# lh.net
KiCad netlist of a schematic drawn in EAGLE
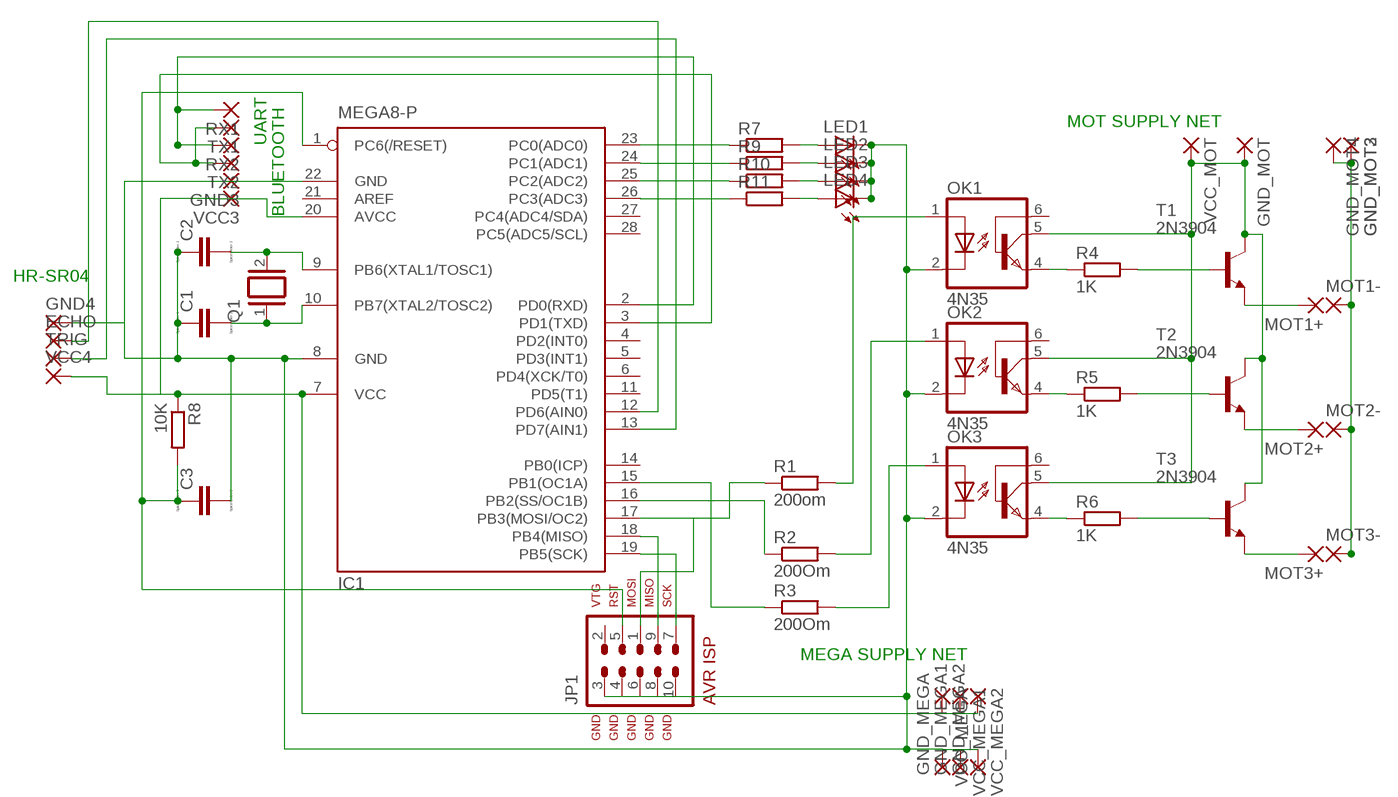
[diagram p0: schematic, sheet 1]

(export (version "E")
  (design (tool "Eeschema 10.0.6"))
  (components
    (comp (ref "C1")
      (value "CC1206")
      (footprint "eagle-import:C1206")
      (libsource (lib "eagle-import") (part "CC1206"))
    )
    (comp (ref "C2")
      (value "CC1206")
      (footprint "eagle-import:C1206")
      (libsource (lib "eagle-import") (part "CC1206"))
    )
    (comp (ref "C3")
      (value "CC1206")
      (footprint "eagle-import:C1206")
      (libsource (lib "eagle-import") (part "CC1206"))
    )
    (comp (ref "ECHO")
      (value "1,6/0,8")
      (footprint "eagle-import:1,6_0,8")
      (libsource (lib "eagle-import") (part "1,6/0,8"))
    )
    (comp (ref "GND3")
      (value "1,6/0,8")
      (footprint "eagle-import:1,6_0,8")
      (libsource (lib "eagle-import") (part "1,6/0,8"))
    )
    (comp (ref "GND4")
      (value "1,6/0,8")
      (footprint "eagle-import:1,6_0,8")
      (libsource (lib "eagle-import") (part "1,6/0,8"))
    )
    (comp (ref "GND_MEGA")
      (value "1,6/0,8")
      (footprint "eagle-import:1,6_0,8")
      (libsource (lib "eagle-import") (part "1,6/0,8"))
    )
    (comp (ref "GND_MEGA1")
      (value "1,6/0,8")
      (footprint "eagle-import:1,6_0,8")
      (libsource (lib "eagle-import") (part "1,6/0,8"))
    )
    (comp (ref "GND_MEGA2")
      (value "1,6/0,8")
      (footprint "eagle-import:1,6_0,8")
      (libsource (lib "eagle-import") (part "1,6/0,8"))
    )
    (comp (ref "GND_MOT")
      (value "1,6/0,8")
      (footprint "eagle-import:1,6_0,8")
      (libsource (lib "eagle-import") (part "1,6/0,8"))
    )
    (comp (ref "GND_MOT2")
      (value "1,6/0,8")
      (footprint "eagle-import:1,6_0,8")
      (libsource (lib "eagle-import") (part "1,6/0,8"))
    )
    (comp (ref "GND_MOT3")
      (value "1,6/0,8")
      (footprint "eagle-import:1,6_0,8")
      (libsource (lib "eagle-import") (part "1,6/0,8"))
    )
    (comp (ref "GND_MOT4")
      (value "1,6/0,8")
      (footprint "eagle-import:1,6_0,8")
      (libsource (lib "eagle-import") (part "1,6/0,8"))
    )
    (comp (ref "IC1")
      (value "MEGA8-P")
      (footprint "eagle-import:DIL28-3")
      (libsource (lib "eagle-import") (part "MEGA8-P"))
    )
    (comp (ref "JP1")
      (value "AVR-ISP-10")
      (footprint "eagle-import:AVR-ISP-10")
      (libsource (lib "eagle-import") (part "AVR-ISP-10"))
    )
    (comp (ref "LED1")
      (value "LEDSML0603")
      (footprint "eagle-import:SML0603")
      (libsource (lib "eagle-import") (part "LEDSML0603"))
    )
    (comp (ref "LED2")
      (value "LEDSML0603")
      (footprint "eagle-import:SML0603")
      (libsource (lib "eagle-import") (part "LEDSML0603"))
    )
    (comp (ref "LED3")
      (value "LEDSML0603")
      (footprint "eagle-import:SML0603")
      (libsource (lib "eagle-import") (part "LEDSML0603"))
    )
    (comp (ref "LED4")
      (value "LEDSML0603")
      (footprint "eagle-import:SML0603")
      (libsource (lib "eagle-import") (part "LEDSML0603"))
    )
    (comp (ref "MOT1+")
      (value "1,6/0,8")
      (footprint "eagle-import:1,6_0,8")
      (libsource (lib "eagle-import") (part "1,6/0,8"))
    )
    (comp (ref "MOT1-")
      (value "1,6/0,8")
      (footprint "eagle-import:1,6_0,8")
      (libsource (lib "eagle-import") (part "1,6/0,8"))
    )
    (comp (ref "MOT2+")
      (value "1,6/0,8")
      (footprint "eagle-import:1,6_0,8")
      (libsource (lib "eagle-import") (part "1,6/0,8"))
    )
    (comp (ref "MOT2-")
      (value "1,6/0,8")
      (footprint "eagle-import:1,6_0,8")
      (libsource (lib "eagle-import") (part "1,6/0,8"))
    )
    (comp (ref "MOT3+")
      (value "1,6/0,8")
      (footprint "eagle-import:1,6_0,8")
      (libsource (lib "eagle-import") (part "1,6/0,8"))
    )
    (comp (ref "MOT3-")
      (value "1,6/0,8")
      (footprint "eagle-import:1,6_0,8")
      (libsource (lib "eagle-import") (part "1,6/0,8"))
    )
    (comp (ref "OK1")
      (value "4N35")
      (footprint "eagle-import:DIL06")
      (fields (field (name "MF") "FAIRCHILD SEMICONDUCTOR"))
      (libsource (lib "eagle-import") (part "4N35"))
    )
    (comp (ref "OK2")
      (value "4N35")
      (footprint "eagle-import:DIL06")
      (fields (field (name "MF") "FAIRCHILD SEMICONDUCTOR"))
      (libsource (lib "eagle-import") (part "4N35"))
    )
    (comp (ref "OK3")
      (value "4N35")
      (footprint "eagle-import:DIL06")
      (fields (field (name "MF") "FAIRCHILD SEMICONDUCTOR"))
      (libsource (lib "eagle-import") (part "4N35"))
    )
    (comp (ref "Q1")
      (value "XTAL/S")
      (footprint "eagle-import:QS")
      (libsource (lib "eagle-import") (part "XTAL/S"))
    )
    (comp (ref "R1")
      (value "200om")
      (footprint "eagle-import:R0603")
      (libsource (lib "eagle-import") (part "R-EU_R0603"))
    )
    (comp (ref "R2")
      (value "200Om")
      (footprint "eagle-import:R0603")
      (libsource (lib "eagle-import") (part "R-EU_R0603"))
    )
    (comp (ref "R3")
      (value "200Om")
      (footprint "eagle-import:R0603")
      (libsource (lib "eagle-import") (part "R-EU_R0603"))
    )
    (comp (ref "R4")
      (value "1K")
      (footprint "eagle-import:R0603")
      (libsource (lib "eagle-import") (part "R-EU_R0603"))
    )
    (comp (ref "R5")
      (value "1K")
      (footprint "eagle-import:R0603")
      (libsource (lib "eagle-import") (part "R-EU_R0603"))
    )
    (comp (ref "R6")
      (value "1K")
      (footprint "eagle-import:R0603")
      (libsource (lib "eagle-import") (part "R-EU_R0603"))
    )
    (comp (ref "R7")
      (value "R-EU_R0603")
      (footprint "eagle-import:R0603")
      (libsource (lib "eagle-import") (part "R-EU_R0603"))
    )
    (comp (ref "R8")
      (value "10K")
      (footprint "eagle-import:R0603")
      (libsource (lib "eagle-import") (part "R-EU_R0603"))
    )
    (comp (ref "R9")
      (value "R-EU_R0603")
      (footprint "eagle-import:R0603")
      (libsource (lib "eagle-import") (part "R-EU_R0603"))
    )
    (comp (ref "R10")
      (value "R-EU_R0603")
      (footprint "eagle-import:R0603")
      (libsource (lib "eagle-import") (part "R-EU_R0603"))
    )
    (comp (ref "R11")
      (value "R-EU_R0603")
      (footprint "eagle-import:R0603")
      (libsource (lib "eagle-import") (part "R-EU_R0603"))
    )
    (comp (ref "RX1")
      (value "1,6/0,8")
      (footprint "eagle-import:1,6_0,8")
      (libsource (lib "eagle-import") (part "1,6/0,8"))
    )
    (comp (ref "RX2")
      (value "1,6/0,8")
      (footprint "eagle-import:1,6_0,8")
      (libsource (lib "eagle-import") (part "1,6/0,8"))
    )
    (comp (ref "T1")
      (value "2N3904")
      (footprint "eagle-import:TO92")
      (libsource (lib "eagle-import") (part "2N3904"))
    )
    (comp (ref "T2")
      (value "2N3904")
      (footprint "eagle-import:TO92")
      (libsource (lib "eagle-import") (part "2N3904"))
    )
    (comp (ref "T3")
      (value "2N3904")
      (footprint "eagle-import:TO92")
      (libsource (lib "eagle-import") (part "2N3904"))
    )
    (comp (ref "TRIG")
      (value "1,6/0,8")
      (footprint "eagle-import:1,6_0,8")
      (libsource (lib "eagle-import") (part "1,6/0,8"))
    )
    (comp (ref "TX1")
      (value "1,6/0,8")
      (footprint "eagle-import:1,6_0,8")
      (libsource (lib "eagle-import") (part "1,6/0,8"))
    )
    (comp (ref "TX2")
      (value "1,6/0,8")
      (footprint "eagle-import:1,6_0,8")
      (libsource (lib "eagle-import") (part "1,6/0,8"))
    )
    (comp (ref "VCC3")
      (value "1,6/0,8")
      (footprint "eagle-import:1,6_0,8")
      (libsource (lib "eagle-import") (part "1,6/0,8"))
    )
    (comp (ref "VCC4")
      (value "1,6/0,8")
      (footprint "eagle-import:1,6_0,8")
      (libsource (lib "eagle-import") (part "1,6/0,8"))
    )
    (comp (ref "VCC_MEGA")
      (value "1,6/0,8")
      (footprint "eagle-import:1,6_0,8")
      (libsource (lib "eagle-import") (part "1,6/0,8"))
    )
    (comp (ref "VCC_MEGA1")
      (value "1,6/0,8")
      (footprint "eagle-import:1,6_0,8")
      (libsource (lib "eagle-import") (part "1,6/0,8"))
    )
    (comp (ref "VCC_MEGA2")
      (value "1,6/0,8")
      (footprint "eagle-import:1,6_0,8")
      (libsource (lib "eagle-import") (part "1,6/0,8"))
    )
    (comp (ref "VCC_MOT")
      (value "1,6/0,8")
      (footprint "eagle-import:1,6_0,8")
      (libsource (lib "eagle-import") (part "1,6/0,8"))
    )
  )
  (nets
    (net (code "1") (name "Net-(ECHO-P)") (class "Default")
      (node (ref "ECHO") (pin "1") (pinfunction "P_1") (pintype "passive"))
      (node (ref "IC1") (pin "12") (pinfunction "PD6(AIN0)_12") (pintype "bidirectional"))
    )
    (net (code "2") (name "Net-(GND3-P)") (class "Default")
      (node (ref "C1") (pin "1") (pinfunction "1_1") (pintype "passive"))
      (node (ref "C2") (pin "1") (pinfunction "1_1") (pintype "passive"))
      (node (ref "C3") (pin "2") (pinfunction "2_2") (pintype "passive"))
      (node (ref "GND3") (pin "1") (pinfunction "P_1") (pintype "passive"))
      (node (ref "GND4") (pin "1") (pinfunction "P_1") (pintype "passive"))
      (node (ref "GND_MEGA") (pin "1") (pinfunction "P_1") (pintype "passive"))
      (node (ref "GND_MEGA1") (pin "1") (pinfunction "P_1") (pintype "passive"))
      (node (ref "GND_MEGA2") (pin "1") (pinfunction "P_1") (pintype "passive"))
      (node (ref "IC1") (pin "22") (pinfunction "GND_22") (pintype "power_in"))
      (node (ref "IC1") (pin "8") (pinfunction "GND_8") (pintype "power_in"))
      (node (ref "JP1") (pin "10") (pinfunction "10_10") (pintype "passive"))
      (node (ref "JP1") (pin "3") (pinfunction "3_3") (pintype "passive"))
      (node (ref "JP1") (pin "4") (pinfunction "4_4") (pintype "passive"))
      (node (ref "JP1") (pin "6") (pinfunction "6_6") (pintype "passive"))
      (node (ref "JP1") (pin "8") (pinfunction "8_8") (pintype "passive"))
      (node (ref "LED1") (pin "C") (pinfunction "C_C") (pintype "passive"))
      (node (ref "LED2") (pin "C") (pinfunction "C_C") (pintype "passive"))
      (node (ref "LED3") (pin "C") (pinfunction "C_C") (pintype "passive"))
      (node (ref "LED4") (pin "C") (pinfunction "C_C") (pintype "passive"))
      (node (ref "OK1") (pin "2") (pinfunction "C_2") (pintype "passive"))
      (node (ref "OK2") (pin "2") (pinfunction "C_2") (pintype "passive"))
      (node (ref "OK3") (pin "2") (pinfunction "C_2") (pintype "passive"))
    )
    (net (code "3") (name "Net-(GND_MOT-P)") (class "Default")
      (node (ref "GND_MOT") (pin "1") (pinfunction "P_1") (pintype "passive"))
      (node (ref "OK1") (pin "5") (pinfunction "COL_5") (pintype "passive"))
      (node (ref "OK2") (pin "5") (pinfunction "COL_5") (pintype "passive"))
      (node (ref "OK3") (pin "5") (pinfunction "COL_5") (pintype "passive"))
      (node (ref "T1") (pin "1") (pinfunction "C_1") (pintype "passive"))
      (node (ref "T2") (pin "1") (pinfunction "C_1") (pintype "passive"))
      (node (ref "T3") (pin "1") (pinfunction "C_1") (pintype "passive"))
      (node (ref "VCC_MOT") (pin "1") (pinfunction "P_1") (pintype "passive"))
    )
    (net (code "4") (name "Net-(GND_MOT2-P)") (class "Default")
      (node (ref "GND_MOT2") (pin "1") (pinfunction "P_1") (pintype "passive"))
      (node (ref "GND_MOT3") (pin "1") (pinfunction "P_1") (pintype "passive"))
      (node (ref "GND_MOT4") (pin "1") (pinfunction "P_1") (pintype "passive"))
      (node (ref "MOT1-") (pin "1") (pinfunction "P_1") (pintype "passive"))
      (node (ref "MOT2-") (pin "1") (pinfunction "P_1") (pintype "passive"))
      (node (ref "MOT3-") (pin "1") (pinfunction "P_1") (pintype "passive"))
    )
    (net (code "5") (name "Net-(IC1-AVCC)") (class "Default")
      (node (ref "IC1") (pin "20") (pinfunction "AVCC_20") (pintype "power_in"))
      (node (ref "IC1") (pin "7") (pinfunction "VCC_7") (pintype "power_in"))
      (node (ref "R8") (pin "1") (pinfunction "1_1") (pintype "passive"))
      (node (ref "VCC3") (pin "1") (pinfunction "P_1") (pintype "passive"))
      (node (ref "VCC4") (pin "1") (pinfunction "P_1") (pintype "passive"))
      (node (ref "VCC_MEGA") (pin "1") (pinfunction "P_1") (pintype "passive"))
      (node (ref "VCC_MEGA1") (pin "1") (pinfunction "P_1") (pintype "passive"))
      (node (ref "VCC_MEGA2") (pin "1") (pinfunction "P_1") (pintype "passive"))
    )
    (net (code "6") (name "Net-(IC1-PB1(OC1A))") (class "Default")
      (node (ref "IC1") (pin "15") (pinfunction "PB1(OC1A)_15") (pintype "bidirectional"))
      (node (ref "R3") (pin "1") (pinfunction "1_1") (pintype "passive"))
    )
    (net (code "7") (name "Net-(IC1-PB2(SS{slash}OC1B))") (class "Default")
      (node (ref "IC1") (pin "16") (pinfunction "PB2(SS/OC1B)_16") (pintype "bidirectional"))
      (node (ref "R2") (pin "1") (pinfunction "1_1") (pintype "passive"))
    )
    (net (code "8") (name "Net-(IC1-PB3(MOSI{slash}OC2))") (class "Default")
      (node (ref "IC1") (pin "17") (pinfunction "PB3(MOSI/OC2)_17") (pintype "bidirectional"))
      (node (ref "R1") (pin "1") (pinfunction "1_1") (pintype "passive"))
    )
    (net (code "9") (name "Net-(IC1-PB4(MISO))") (class "Default")
      (node (ref "IC1") (pin "18") (pinfunction "PB4(MISO)_18") (pintype "bidirectional"))
      (node (ref "JP1") (pin "9") (pinfunction "9_9") (pintype "passive"))
    )
    (net (code "10") (name "Net-(IC1-PB5(SCK))") (class "Default")
      (node (ref "IC1") (pin "19") (pinfunction "PB5(SCK)_19") (pintype "bidirectional"))
      (node (ref "JP1") (pin "7") (pinfunction "7_7") (pintype "passive"))
    )
    (net (code "11") (name "Net-(IC1-PB6(XTAL1{slash}TOSC1))") (class "Default")
      (node (ref "C2") (pin "2") (pinfunction "2_2") (pintype "passive"))
      (node (ref "IC1") (pin "9") (pinfunction "PB6(XTAL1/TOSC1)_9") (pintype "bidirectional"))
      (node (ref "Q1") (pin "2") (pinfunction "2_2") (pintype "passive"))
    )
    (net (code "12") (name "Net-(IC1-PB7(XTAL2{slash}TOSC2))") (class "Default")
      (node (ref "C1") (pin "2") (pinfunction "2_2") (pintype "passive"))
      (node (ref "IC1") (pin "10") (pinfunction "PB7(XTAL2/TOSC2)_10") (pintype "bidirectional"))
      (node (ref "Q1") (pin "1") (pinfunction "1_1") (pintype "passive"))
    )
    (net (code "13") (name "Net-(IC1-PC0(ADC0))") (class "Default")
      (node (ref "IC1") (pin "23") (pinfunction "PC0(ADC0)_23") (pintype "bidirectional"))
      (node (ref "R7") (pin "1") (pinfunction "1_1") (pintype "passive"))
    )
    (net (code "14") (name "Net-(IC1-PC1(ADC1))") (class "Default")
      (node (ref "IC1") (pin "24") (pinfunction "PC1(ADC1)_24") (pintype "bidirectional"))
      (node (ref "R9") (pin "1") (pinfunction "1_1") (pintype "passive"))
    )
    (net (code "15") (name "Net-(IC1-PC2(ADC2))") (class "Default")
      (node (ref "IC1") (pin "25") (pinfunction "PC2(ADC2)_25") (pintype "bidirectional"))
      (node (ref "R10") (pin "1") (pinfunction "1_1") (pintype "passive"))
    )
    (net (code "16") (name "Net-(IC1-PC3(ADC3))") (class "Default")
      (node (ref "IC1") (pin "26") (pinfunction "PC3(ADC3)_26") (pintype "bidirectional"))
      (node (ref "R11") (pin "1") (pinfunction "1_1") (pintype "passive"))
    )
    (net (code "17") (name "Net-(IC1-PC6({slash}RESET))") (class "Default")
      (node (ref "C3") (pin "1") (pinfunction "1_1") (pintype "passive"))
      (node (ref "IC1") (pin "1") (pinfunction "PC6(/RESET)_1") (pintype "bidirectional"))
      (node (ref "JP1") (pin "5") (pinfunction "5_5") (pintype "passive"))
      (node (ref "R8") (pin "2") (pinfunction "2_2") (pintype "passive"))
    )
    (net (code "18") (name "Net-(IC1-PD0(RXD))") (class "Default")
      (node (ref "IC1") (pin "2") (pinfunction "PD0(RXD)_2") (pintype "bidirectional"))
      (node (ref "RX1") (pin "1") (pinfunction "P_1") (pintype "passive"))
      (node (ref "RX2") (pin "1") (pinfunction "P_1") (pintype "passive"))
    )
    (net (code "19") (name "Net-(IC1-PD1(TXD))") (class "Default")
      (node (ref "IC1") (pin "3") (pinfunction "PD1(TXD)_3") (pintype "bidirectional"))
      (node (ref "TX1") (pin "1") (pinfunction "P_1") (pintype "passive"))
      (node (ref "TX2") (pin "1") (pinfunction "P_1") (pintype "passive"))
    )
    (net (code "20") (name "Net-(IC1-PD7(AIN1))") (class "Default")
      (node (ref "IC1") (pin "13") (pinfunction "PD7(AIN1)_13") (pintype "bidirectional"))
      (node (ref "TRIG") (pin "1") (pinfunction "P_1") (pintype "passive"))
    )
    (net (code "21") (name "Net-(LED1-PadA)") (class "Default")
      (node (ref "LED1") (pin "A") (pinfunction "A_A") (pintype "passive"))
      (node (ref "R7") (pin "2") (pinfunction "2_2") (pintype "passive"))
    )
    (net (code "22") (name "Net-(LED2-PadA)") (class "Default")
      (node (ref "LED2") (pin "A") (pinfunction "A_A") (pintype "passive"))
      (node (ref "R9") (pin "2") (pinfunction "2_2") (pintype "passive"))
    )
    (net (code "23") (name "Net-(LED3-PadA)") (class "Default")
      (node (ref "LED3") (pin "A") (pinfunction "A_A") (pintype "passive"))
      (node (ref "R10") (pin "2") (pinfunction "2_2") (pintype "passive"))
    )
    (net (code "24") (name "Net-(LED4-PadA)") (class "Default")
      (node (ref "LED4") (pin "A") (pinfunction "A_A") (pintype "passive"))
      (node (ref "R11") (pin "2") (pinfunction "2_2") (pintype "passive"))
    )
    (net (code "25") (name "Net-(MOT1+-P)") (class "Default")
      (node (ref "MOT1+") (pin "1") (pinfunction "P_1") (pintype "passive"))
      (node (ref "T1") (pin "3") (pinfunction "E_3") (pintype "passive"))
    )
    (net (code "26") (name "Net-(MOT2+-P)") (class "Default")
      (node (ref "MOT2+") (pin "1") (pinfunction "P_1") (pintype "passive"))
      (node (ref "T2") (pin "3") (pinfunction "E_3") (pintype "passive"))
    )
    (net (code "27") (name "Net-(MOT3+-P)") (class "Default")
      (node (ref "MOT3+") (pin "1") (pinfunction "P_1") (pintype "passive"))
      (node (ref "T3") (pin "3") (pinfunction "E_3") (pintype "passive"))
    )
    (net (code "28") (name "Net-(OK1-A)") (class "Default")
      (node (ref "OK1") (pin "1") (pinfunction "A_1") (pintype "passive"))
      (node (ref "R1") (pin "2") (pinfunction "2_2") (pintype "passive"))
    )
    (net (code "29") (name "Net-(OK1-EMI)") (class "Default")
      (node (ref "OK1") (pin "4") (pinfunction "EMI_4") (pintype "passive"))
      (node (ref "R4") (pin "1") (pinfunction "1_1") (pintype "passive"))
    )
    (net (code "30") (name "Net-(OK2-A)") (class "Default")
      (node (ref "OK2") (pin "1") (pinfunction "A_1") (pintype "passive"))
      (node (ref "R2") (pin "2") (pinfunction "2_2") (pintype "passive"))
    )
    (net (code "31") (name "Net-(OK2-EMI)") (class "Default")
      (node (ref "OK2") (pin "4") (pinfunction "EMI_4") (pintype "passive"))
      (node (ref "R5") (pin "1") (pinfunction "1_1") (pintype "passive"))
    )
    (net (code "32") (name "Net-(OK3-A)") (class "Default")
      (node (ref "OK3") (pin "1") (pinfunction "A_1") (pintype "passive"))
      (node (ref "R3") (pin "2") (pinfunction "2_2") (pintype "passive"))
    )
    (net (code "33") (name "Net-(OK3-EMI)") (class "Default")
      (node (ref "OK3") (pin "4") (pinfunction "EMI_4") (pintype "passive"))
      (node (ref "R6") (pin "1") (pinfunction "1_1") (pintype "passive"))
    )
    (net (code "34") (name "Net-(T1-B)") (class "Default")
      (node (ref "R4") (pin "2") (pinfunction "2_2") (pintype "passive"))
      (node (ref "T1") (pin "2") (pinfunction "B_2") (pintype "passive"))
    )
    (net (code "35") (name "Net-(T2-B)") (class "Default")
      (node (ref "R5") (pin "2") (pinfunction "2_2") (pintype "passive"))
      (node (ref "T2") (pin "2") (pinfunction "B_2") (pintype "passive"))
    )
    (net (code "36") (name "Net-(T3-B)") (class "Default")
      (node (ref "R6") (pin "2") (pinfunction "2_2") (pintype "passive"))
      (node (ref "T3") (pin "2") (pinfunction "B_2") (pintype "passive"))
    )
    (net (code "37") (name "unconnected-(IC1-AREF-Pad21)") (class "Default")
      (node (ref "IC1") (pin "21") (pinfunction "AREF_21") (pintype "passive"))
    )
    (net (code "38") (name "unconnected-(IC1-PB0(ICP)-Pad14)") (class "Default")
      (node (ref "IC1") (pin "14") (pinfunction "PB0(ICP)_14") (pintype "bidirectional"))
    )
    (net (code "39") (name "unconnected-(IC1-PC4(ADC4{slash}SDA)-Pad27)") (class "Default")
      (node (ref "IC1") (pin "27") (pinfunction "PC4(ADC4/SDA)_27") (pintype "bidirectional"))
    )
    (net (code "40") (name "unconnected-(IC1-PC5(ADC5{slash}SCL)-Pad28)") (class "Default")
      (node (ref "IC1") (pin "28") (pinfunction "PC5(ADC5/SCL)_28") (pintype "bidirectional"))
    )
    (net (code "41") (name "unconnected-(IC1-PD2(INT0)-Pad4)") (class "Default")
      (node (ref "IC1") (pin "4") (pinfunction "PD2(INT0)_4") (pintype "bidirectional"))
    )
    (net (code "42") (name "unconnected-(IC1-PD3(INT1)-Pad5)") (class "Default")
      (node (ref "IC1") (pin "5") (pinfunction "PD3(INT1)_5") (pintype "bidirectional"))
    )
    (net (code "43") (name "unconnected-(IC1-PD4(XCK{slash}T0)-Pad6)") (class "Default")
      (node (ref "IC1") (pin "6") (pinfunction "PD4(XCK/T0)_6") (pintype "bidirectional"))
    )
    (net (code "44") (name "unconnected-(IC1-PD5(T1)-Pad11)") (class "Default")
      (node (ref "IC1") (pin "11") (pinfunction "PD5(T1)_11") (pintype "bidirectional"))
    )
    (net (code "45") (name "unconnected-(JP1-Pad1)") (class "Default")
      (node (ref "JP1") (pin "1") (pinfunction "1_1") (pintype "passive"))
    )
    (net (code "46") (name "unconnected-(JP1-Pad2)") (class "Default")
      (node (ref "JP1") (pin "2") (pinfunction "2_2") (pintype "passive"))
    )
    (net (code "47") (name "unconnected-(OK1-BAS-Pad6)") (class "Default")
      (node (ref "OK1") (pin "6") (pinfunction "BAS_6") (pintype "passive"))
    )
    (net (code "48") (name "unconnected-(OK2-BAS-Pad6)") (class "Default")
      (node (ref "OK2") (pin "6") (pinfunction "BAS_6") (pintype "passive"))
    )
    (net (code "49") (name "unconnected-(OK3-BAS-Pad6)") (class "Default")
      (node (ref "OK3") (pin "6") (pinfunction "BAS_6") (pintype "passive"))
    )
  )
)
